# water-pump.net
KiCad netlist of a schematic drawn in EAGLE
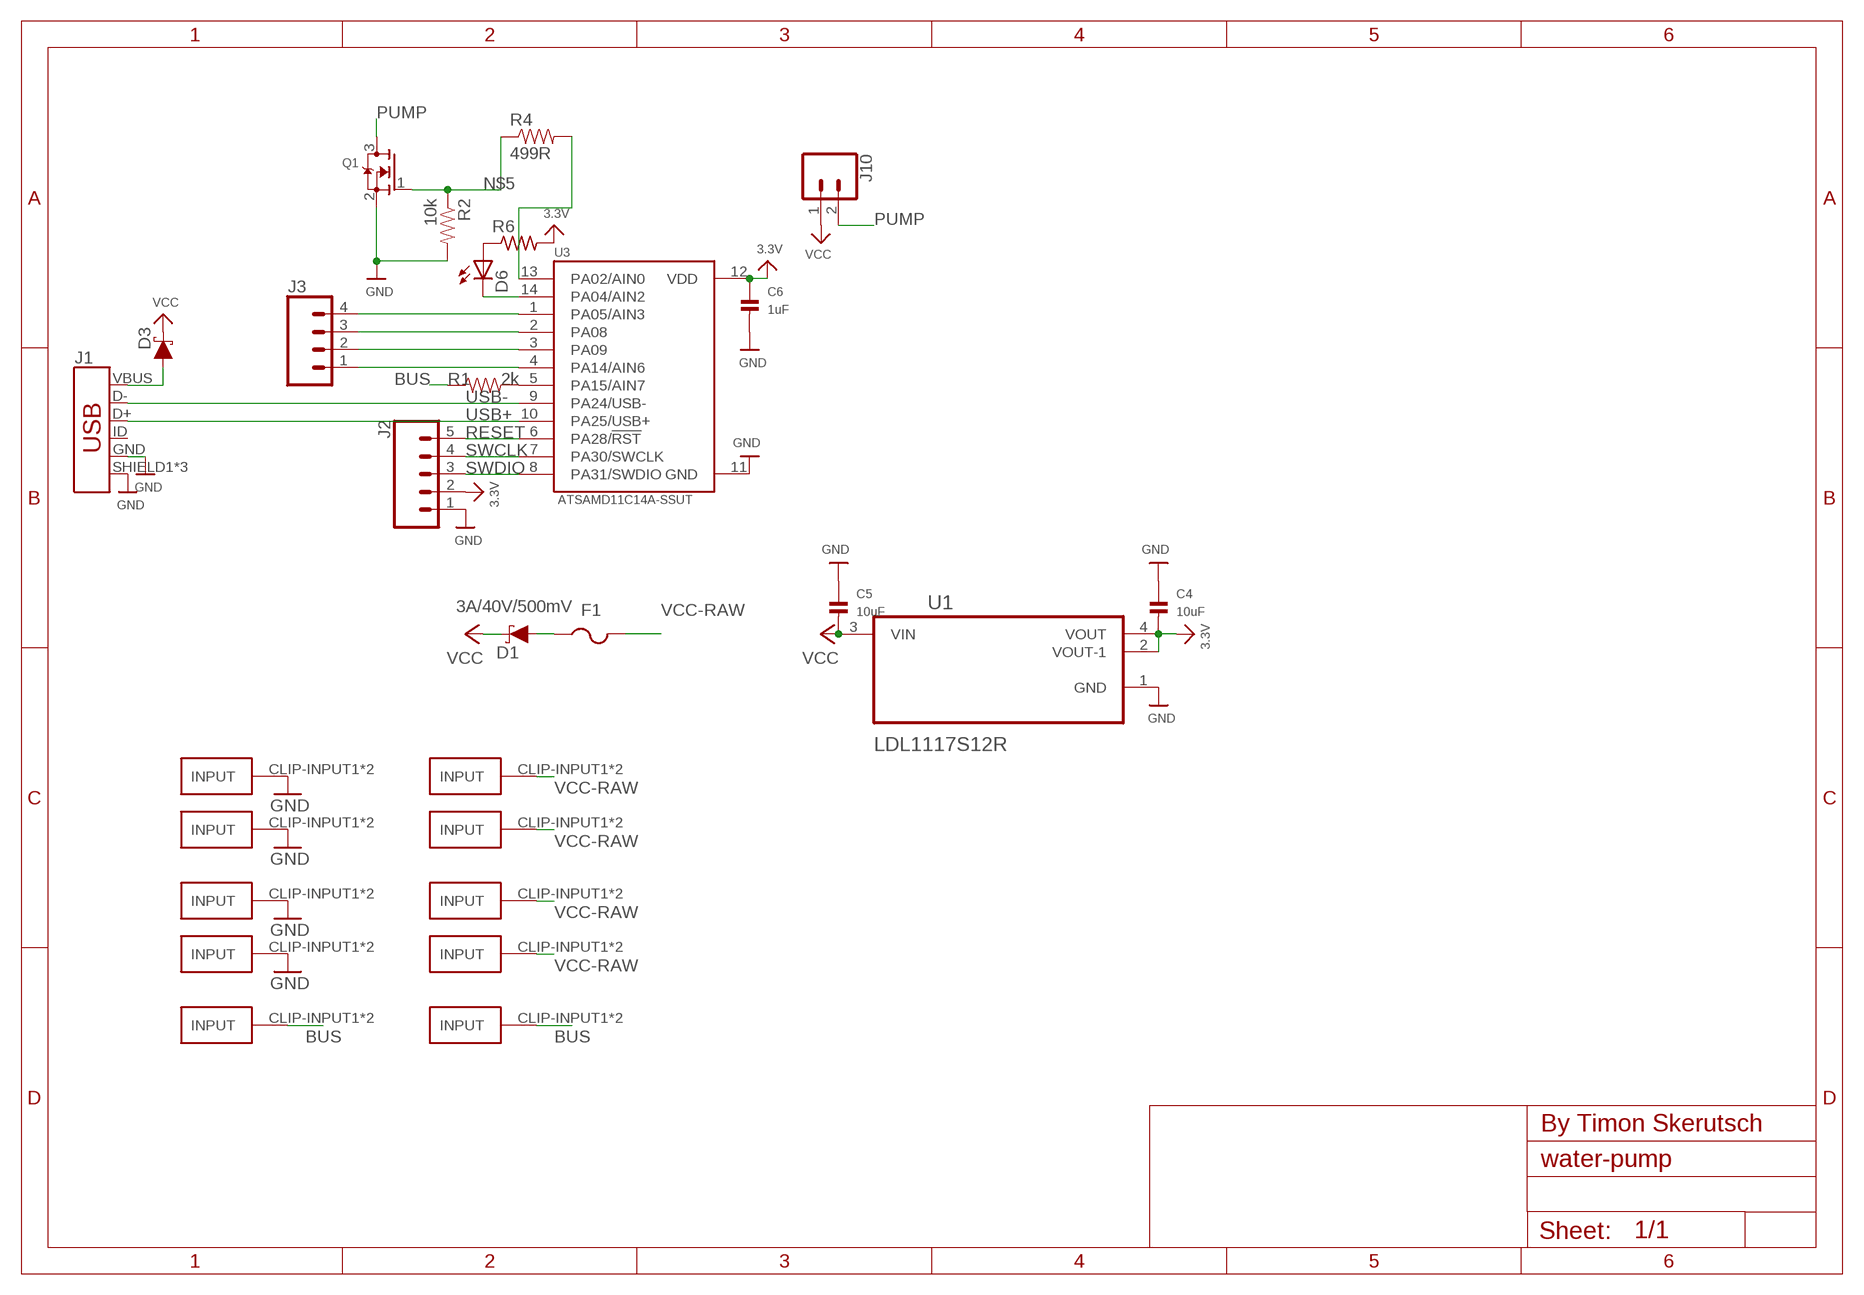
[diagram p0: schematic, sheet 1]

(export (version "E")
  (design (tool "Eeschema 10.0.6"))
  (components
    (comp (ref "C4")
      (value "10uF")
      (footprint "eagle-import:0805")
      (libsource (lib "eagle-import") (part "CAP_CERAMIC0805"))
    )
    (comp (ref "C5")
      (value "10uF")
      (footprint "eagle-import:0805")
      (libsource (lib "eagle-import") (part "CAP_CERAMIC0805"))
    )
    (comp (ref "C6")
      (value "1uF")
      (footprint "eagle-import:0603")
      (libsource (lib "eagle-import") (part "CAP_CERAMIC0603"))
    )
    (comp (ref "D1")
      (value "3A/40V/500mV")
      (footprint "eagle-import:SMA-DIODE")
      (libsource (lib "eagle-import") (part "DIODE-SCHOTTKY-B340A"))
    )
    (comp (ref "D3")
      (value "3A/40V/500mV")
      (footprint "eagle-import:SMA-DIODE")
      (libsource (lib "eagle-import") (part "DIODE-SCHOTTKY-B340A"))
    )
    (comp (ref "D6")
      (value "LEDCHIPLED_0805")
      (footprint "eagle-import:CHIPLED_0805")
      (libsource (lib "eagle-import") (part "LEDCHIPLED_0805"))
    )
    (comp (ref "F1")
      (value "PTCFUSE-1812")
      (footprint "eagle-import:1812")
      (libsource (lib "eagle-import") (part "PTCFUSE-1812"))
    )
    (comp (ref "GND-CLIP")
      (value "FUSE-HOLDER-5X20MM")
      (footprint "eagle-import:FUSE-HOLDER-5X20MM")
      (libsource (lib "eagle-import") (part "FUSE-HOLDER-5X20MM"))
    )
    (comp (ref "GND-CLIP1")
      (value "FUSE-HOLDER-5X20MM")
      (footprint "eagle-import:FUSE-HOLDER-5X20MM")
      (libsource (lib "eagle-import") (part "FUSE-HOLDER-5X20MM"))
    )
    (comp (ref "GND-CLIP2")
      (value "FUSE-HOLDER-5X20MM")
      (footprint "eagle-import:FUSE-HOLDER-5X20MM")
      (libsource (lib "eagle-import") (part "FUSE-HOLDER-5X20MM"))
    )
    (comp (ref "GND-CLIP3")
      (value "FUSE-HOLDER-5X20MM")
      (footprint "eagle-import:FUSE-HOLDER-5X20MM")
      (libsource (lib "eagle-import") (part "FUSE-HOLDER-5X20MM"))
    )
    (comp (ref "J1")
      (value "USB_MICRO-B_FEMALE-SMT")
      (footprint "eagle-import:USB-B-MICRO-SMD")
      (libsource (lib "eagle-import") (part "USB_MICRO-B_FEMALE-SMT"))
    )
    (comp (ref "J2")
      (value "CONN_05")
      (footprint "eagle-import:1X05")
      (libsource (lib "eagle-import") (part "CONN_05"))
    )
    (comp (ref "J3")
      (value "CONN_04PTH")
      (footprint "eagle-import:1X04")
      (libsource (lib "eagle-import") (part "CONN_04PTH"))
    )
    (comp (ref "J10")
      (value "CONN_02PTH3")
      (footprint "eagle-import:1X02_LONGPADS")
      (libsource (lib "eagle-import") (part "CONN_02PTH3"))
    )
    (comp (ref "PWM-CLIP")
      (value "FUSE-HOLDER-5X20MM")
      (footprint "eagle-import:FUSE-HOLDER-5X20MM")
      (libsource (lib "eagle-import") (part "FUSE-HOLDER-5X20MM"))
    )
    (comp (ref "PWM-CLIP1")
      (value "FUSE-HOLDER-5X20MM")
      (footprint "eagle-import:FUSE-HOLDER-5X20MM")
      (libsource (lib "eagle-import") (part "FUSE-HOLDER-5X20MM"))
    )
    (comp (ref "Q1")
      (value "MOSFET-NWIDE")
      (footprint "eagle-import:SOT23-WIDE")
      (libsource (lib "eagle-import") (part "MOSFET-NWIDE"))
    )
    (comp (ref "R1")
      (value "2k")
      (footprint "eagle-import:1206")
      (libsource (lib "eagle-import") (part "RESISTOR1206"))
    )
    (comp (ref "R2")
      (value "10k")
      (footprint "eagle-import:1206")
      (libsource (lib "eagle-import") (part "RESISTOR1206"))
    )
    (comp (ref "R4")
      (value "499R")
      (footprint "eagle-import:1206")
      (libsource (lib "eagle-import") (part "RESISTOR1206"))
    )
    (comp (ref "R6")
      (value "R-US_R0805")
      (footprint "eagle-import:R0805")
      (libsource (lib "eagle-import") (part "R-US_R0805"))
    )
    (comp (ref "U1")
      (value "LDL1117S12R")
      (footprint "eagle-import:SOT230P700X180-4N")
      (fields (field (name "MF") "STMicroelectronics"))
      (libsource (lib "eagle-import") (part "LDL1117S12R"))
    )
    (comp (ref "U3")
      (value "ATSAMD11C14A-SSUT")
      (footprint "eagle-import:SOIC127P600X160-14N")
      (fields (field (name "MF") "Microchip"))
      (libsource (lib "eagle-import") (part "ATSAMD11C14A-SSUT"))
    )
    (comp (ref "VCC-CLIP")
      (value "FUSE-HOLDER-5X20MM")
      (footprint "eagle-import:FUSE-HOLDER-5X20MM")
      (libsource (lib "eagle-import") (part "FUSE-HOLDER-5X20MM"))
    )
    (comp (ref "VCC-CLIP1")
      (value "FUSE-HOLDER-5X20MM")
      (footprint "eagle-import:FUSE-HOLDER-5X20MM")
      (libsource (lib "eagle-import") (part "FUSE-HOLDER-5X20MM"))
    )
    (comp (ref "VCC-CLIP2")
      (value "FUSE-HOLDER-5X20MM")
      (footprint "eagle-import:FUSE-HOLDER-5X20MM")
      (libsource (lib "eagle-import") (part "FUSE-HOLDER-5X20MM"))
    )
    (comp (ref "VCC-CLIP3")
      (value "FUSE-HOLDER-5X20MM")
      (footprint "eagle-import:FUSE-HOLDER-5X20MM")
      (libsource (lib "eagle-import") (part "FUSE-HOLDER-5X20MM"))
    )
  )
  (nets
    (net (code "1") (name "/BUS") (class "Default")
      (node (ref "PWM-CLIP") (pin "CLIP-INPUT1") (pinfunction "INPUT_CLIP-INPUT1") (pintype "bidirectional"))
      (node (ref "PWM-CLIP") (pin "CLIP-INPUT2") (pinfunction "INPUT_CLIP-INPUT2") (pintype "bidirectional"))
      (node (ref "PWM-CLIP1") (pin "CLIP-INPUT1") (pinfunction "INPUT_CLIP-INPUT1") (pintype "bidirectional"))
      (node (ref "PWM-CLIP1") (pin "CLIP-INPUT2") (pinfunction "INPUT_CLIP-INPUT2") (pintype "bidirectional"))
      (node (ref "R1") (pin "1") (pinfunction "1_1") (pintype "passive"))
    )
    (net (code "2") (name "/N$5") (class "Default")
      (node (ref "Q1") (pin "1") (pinfunction "G_1") (pintype "bidirectional"))
      (node (ref "R2") (pin "1") (pinfunction "1_1") (pintype "passive"))
      (node (ref "R4") (pin "1") (pinfunction "1_1") (pintype "passive"))
    )
    (net (code "3") (name "/PUMP") (class "Default")
      (node (ref "J10") (pin "2") (pinfunction "2_2") (pintype "passive"))
      (node (ref "Q1") (pin "3") (pinfunction "D_3") (pintype "bidirectional"))
    )
    (net (code "4") (name "/RESET") (class "Default")
      (node (ref "J2") (pin "5") (pinfunction "5_5") (pintype "passive"))
      (node (ref "U3") (pin "6") (pinfunction "PA28/~{RST}_6") (pintype "bidirectional"))
    )
    (net (code "5") (name "/SWCLK") (class "Default")
      (node (ref "J2") (pin "4") (pinfunction "4_4") (pintype "passive"))
      (node (ref "U3") (pin "7") (pinfunction "PA30/SWCLK_7") (pintype "bidirectional"))
    )
    (net (code "6") (name "/SWDIO") (class "Default")
      (node (ref "J2") (pin "3") (pinfunction "3_3") (pintype "passive"))
      (node (ref "U3") (pin "8") (pinfunction "PA31/SWDIO_8") (pintype "bidirectional"))
    )
    (net (code "7") (name "/USB+") (class "Default")
      (node (ref "J1") (pin "D+") (pinfunction "D+_D+") (pintype "bidirectional"))
      (node (ref "U3") (pin "10") (pinfunction "PA25/USB+_10") (pintype "bidirectional"))
    )
    (net (code "8") (name "/USB-") (class "Default")
      (node (ref "J1") (pin "D-") (pinfunction "D-_D-") (pintype "bidirectional"))
      (node (ref "U3") (pin "9") (pinfunction "PA24/USB-_9") (pintype "bidirectional"))
    )
    (net (code "9") (name "/VCC-RAW") (class "Default")
      (node (ref "F1") (pin "2") (pinfunction "2_2") (pintype "passive"))
      (node (ref "VCC-CLIP") (pin "CLIP-INPUT1") (pinfunction "INPUT_CLIP-INPUT1") (pintype "bidirectional"))
      (node (ref "VCC-CLIP") (pin "CLIP-INPUT2") (pinfunction "INPUT_CLIP-INPUT2") (pintype "bidirectional"))
      (node (ref "VCC-CLIP1") (pin "CLIP-INPUT1") (pinfunction "INPUT_CLIP-INPUT1") (pintype "bidirectional"))
      (node (ref "VCC-CLIP1") (pin "CLIP-INPUT2") (pinfunction "INPUT_CLIP-INPUT2") (pintype "bidirectional"))
      (node (ref "VCC-CLIP2") (pin "CLIP-INPUT1") (pinfunction "INPUT_CLIP-INPUT1") (pintype "bidirectional"))
      (node (ref "VCC-CLIP2") (pin "CLIP-INPUT2") (pinfunction "INPUT_CLIP-INPUT2") (pintype "bidirectional"))
      (node (ref "VCC-CLIP3") (pin "CLIP-INPUT1") (pinfunction "INPUT_CLIP-INPUT1") (pintype "bidirectional"))
      (node (ref "VCC-CLIP3") (pin "CLIP-INPUT2") (pinfunction "INPUT_CLIP-INPUT2") (pintype "bidirectional"))
    )
    (net (code "10") (name "3.3V") (class "Default")
      (node (ref "C4") (pin "2") (pinfunction "P$2_2") (pintype "passive"))
      (node (ref "C6") (pin "1") (pinfunction "P$1_1") (pintype "passive"))
      (node (ref "J2") (pin "2") (pinfunction "2_2") (pintype "passive"))
      (node (ref "R6") (pin "2") (pinfunction "2_2") (pintype "passive"))
      (node (ref "U1") (pin "2") (pinfunction "VOUT-1_2") (pintype "output"))
      (node (ref "U1") (pin "4") (pinfunction "VOUT_4") (pintype "output"))
      (node (ref "U3") (pin "12") (pinfunction "VDD_12") (pintype "power_in"))
    )
    (net (code "11") (name "GND") (class "Default")
      (node (ref "C4") (pin "1") (pinfunction "P$1_1") (pintype "passive"))
      (node (ref "C5") (pin "1") (pinfunction "P$1_1") (pintype "passive"))
      (node (ref "C6") (pin "2") (pinfunction "P$2_2") (pintype "passive"))
      (node (ref "GND-CLIP") (pin "CLIP-INPUT1") (pinfunction "INPUT_CLIP-INPUT1") (pintype "bidirectional"))
      (node (ref "GND-CLIP") (pin "CLIP-INPUT2") (pinfunction "INPUT_CLIP-INPUT2") (pintype "bidirectional"))
      (node (ref "GND-CLIP1") (pin "CLIP-INPUT1") (pinfunction "INPUT_CLIP-INPUT1") (pintype "bidirectional"))
      (node (ref "GND-CLIP1") (pin "CLIP-INPUT2") (pinfunction "INPUT_CLIP-INPUT2") (pintype "bidirectional"))
      (node (ref "GND-CLIP2") (pin "CLIP-INPUT1") (pinfunction "INPUT_CLIP-INPUT1") (pintype "bidirectional"))
      (node (ref "GND-CLIP2") (pin "CLIP-INPUT2") (pinfunction "INPUT_CLIP-INPUT2") (pintype "bidirectional"))
      (node (ref "GND-CLIP3") (pin "CLIP-INPUT1") (pinfunction "INPUT_CLIP-INPUT1") (pintype "bidirectional"))
      (node (ref "GND-CLIP3") (pin "CLIP-INPUT2") (pinfunction "INPUT_CLIP-INPUT2") (pintype "bidirectional"))
      (node (ref "J1") (pin "GND") (pinfunction "GND_GND") (pintype "power_in"))
      (node (ref "J1") (pin "SHIELD1") (pinfunction "SHIELD_SHIELD1") (pintype "bidirectional"))
      (node (ref "J1") (pin "SHIELD2") (pinfunction "SHIELD_SHIELD2") (pintype "bidirectional"))
      (node (ref "J1") (pin "SHIELD3") (pinfunction "SHIELD_SHIELD3") (pintype "bidirectional"))
      (node (ref "J2") (pin "1") (pinfunction "1_1") (pintype "passive"))
      (node (ref "Q1") (pin "2") (pinfunction "S_2") (pintype "bidirectional"))
      (node (ref "R2") (pin "2") (pinfunction "2_2") (pintype "passive"))
      (node (ref "U1") (pin "1") (pinfunction "GND_1") (pintype "power_in"))
      (node (ref "U3") (pin "11") (pinfunction "GND_11") (pintype "power_in"))
    )
    (net (code "12") (name "Net-(D1-PadA)") (class "Default")
      (node (ref "D1") (pin "A") (pinfunction "A_A") (pintype "passive"))
      (node (ref "F1") (pin "1") (pinfunction "1_1") (pintype "passive"))
    )
    (net (code "13") (name "Net-(D3-PadA)") (class "Default")
      (node (ref "D3") (pin "A") (pinfunction "A_A") (pintype "passive"))
      (node (ref "J1") (pin "VBUS") (pinfunction "VBUS_VBUS") (pintype "power_in"))
    )
    (net (code "14") (name "Net-(D6-PadA)") (class "Default")
      (node (ref "D6") (pin "A") (pinfunction "A_A") (pintype "passive"))
      (node (ref "R6") (pin "1") (pinfunction "1_1") (pintype "passive"))
    )
    (net (code "15") (name "Net-(U3-PA02{slash}AIN0)") (class "Default")
      (node (ref "R4") (pin "2") (pinfunction "2_2") (pintype "passive"))
      (node (ref "U3") (pin "13") (pinfunction "PA02/AIN0_13") (pintype "bidirectional"))
    )
    (net (code "16") (name "Net-(U3-PA04{slash}AIN2)") (class "Default")
      (node (ref "D6") (pin "C") (pinfunction "C_C") (pintype "passive"))
      (node (ref "U3") (pin "14") (pinfunction "PA04/AIN2_14") (pintype "bidirectional"))
    )
    (net (code "17") (name "Net-(U3-PA05{slash}AIN3)") (class "Default")
      (node (ref "J3") (pin "4") (pinfunction "4_4") (pintype "passive"))
      (node (ref "U3") (pin "1") (pinfunction "PA05/AIN3_1") (pintype "bidirectional"))
    )
    (net (code "18") (name "Net-(U3-PA08)") (class "Default")
      (node (ref "J3") (pin "3") (pinfunction "3_3") (pintype "passive"))
      (node (ref "U3") (pin "2") (pinfunction "PA08_2") (pintype "bidirectional"))
    )
    (net (code "19") (name "Net-(U3-PA09)") (class "Default")
      (node (ref "J3") (pin "2") (pinfunction "2_2") (pintype "passive"))
      (node (ref "U3") (pin "3") (pinfunction "PA09_3") (pintype "bidirectional"))
    )
    (net (code "20") (name "Net-(U3-PA14{slash}AIN6)") (class "Default")
      (node (ref "J3") (pin "1") (pinfunction "1_1") (pintype "passive"))
      (node (ref "U3") (pin "4") (pinfunction "PA14/AIN6_4") (pintype "bidirectional"))
    )
    (net (code "21") (name "Net-(U3-PA15{slash}AIN7)") (class "Default")
      (node (ref "R1") (pin "2") (pinfunction "2_2") (pintype "passive"))
      (node (ref "U3") (pin "5") (pinfunction "PA15/AIN7_5") (pintype "bidirectional"))
    )
    (net (code "22") (name "VCC") (class "Default")
      (node (ref "C5") (pin "2") (pinfunction "P$2_2") (pintype "passive"))
      (node (ref "D1") (pin "C") (pinfunction "C_C") (pintype "passive"))
      (node (ref "D3") (pin "C") (pinfunction "C_C") (pintype "passive"))
      (node (ref "J10") (pin "1") (pinfunction "1_1") (pintype "passive"))
      (node (ref "U1") (pin "3") (pinfunction "VIN_3") (pintype "input"))
    )
    (net (code "23") (name "unconnected-(J1-PadID)") (class "Default")
      (node (ref "J1") (pin "ID") (pinfunction "ID_ID") (pintype "bidirectional"))
    )
  )
)
